# FOTA_Micro_Controller.net
KiCad netlist of a schematic drawn in Altium Designer
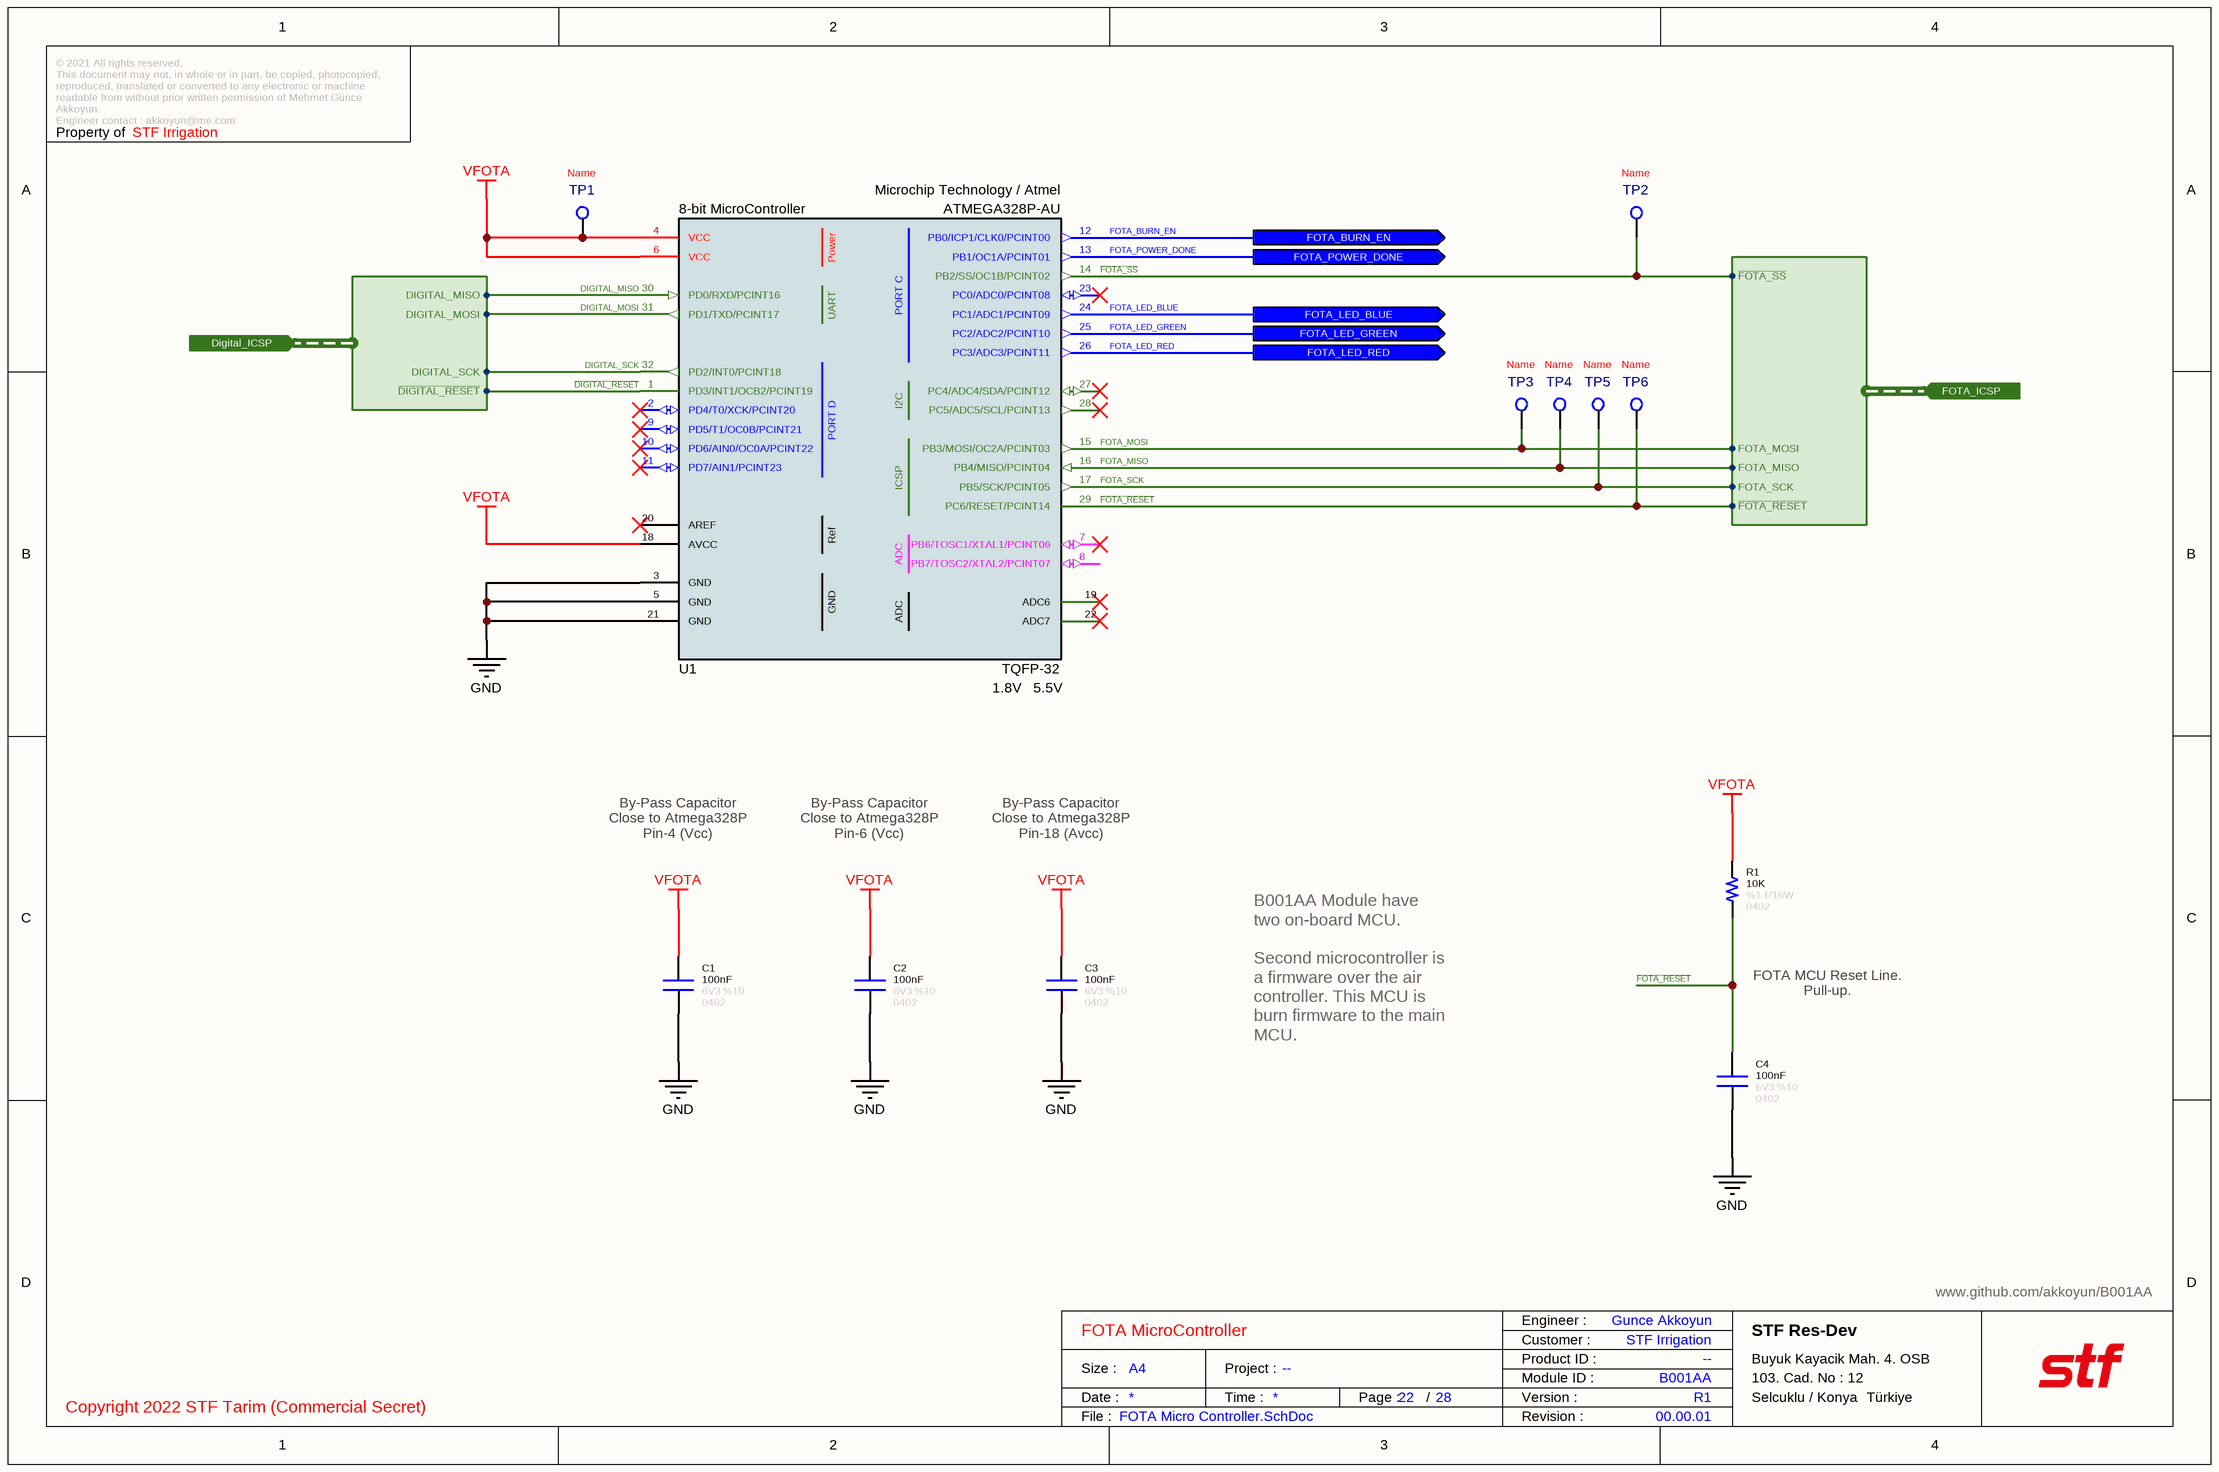
[diagram p0: FOTA Micro Controller.SchDoc]

(export (version "E")
  (design (tool "Eeschema 10.0.6"))
  (components
    (comp (ref "C1")
      (value "100nF")
      (footprint "CAPACITOR_0402")
      (description "Capacitor - 100nF [0402-6V3] (Ceramic)")
      (fields
        (field (name "MANUFACTURER PART NUMBER") "04026D104KAT4A")
        (field (name "TOLERANCE") "%10")
        (field (name "VOLTAGE") "6V3")
        (field (name "CASE") "0402")
        (field (name "Comment") "Capacitor - 100nF [0402] (Ceramic)")
      )
      (libsource (lib "P101DA_Library") (part "Capacitor - 100nF [0402-6V3]"))
    )
    (comp (ref "C2")
      (value "100nF")
      (footprint "CAPACITOR_0402")
      (description "Capacitor - 100nF [0402-6V3] (Ceramic)")
      (fields
        (field (name "MANUFACTURER PART NUMBER") "04026D104KAT4A")
        (field (name "TOLERANCE") "%10")
        (field (name "VOLTAGE") "6V3")
        (field (name "CASE") "0402")
        (field (name "Comment") "Capacitor - 100nF [0402] (Ceramic)")
      )
      (libsource (lib "P101DA_Library") (part "Capacitor - 100nF [0402-6V3]"))
    )
    (comp (ref "C3")
      (value "100nF")
      (footprint "CAPACITOR_0402")
      (description "Capacitor - 100nF [0402-6V3] (Ceramic)")
      (fields
        (field (name "MANUFACTURER PART NUMBER") "04026D104KAT4A")
        (field (name "TOLERANCE") "%10")
        (field (name "VOLTAGE") "6V3")
        (field (name "CASE") "0402")
        (field (name "Comment") "Capacitor - 100nF [0402] (Ceramic)")
      )
      (libsource (lib "P101DA_Library") (part "Capacitor - 100nF [0402-6V3]"))
    )
    (comp (ref "C4")
      (value "100nF")
      (footprint "CAPACITOR_0402")
      (description "Capacitor - 100nF [0402-6V3] (Ceramic)")
      (fields
        (field (name "MANUFACTURER PART NUMBER") "04026D104KAT4A")
        (field (name "TOLERANCE") "%10")
        (field (name "VOLTAGE") "6V3")
        (field (name "CASE") "0402")
        (field (name "Comment") "Capacitor - 100nF [0402] (Ceramic)")
      )
      (libsource (lib "P101DA_Library") (part "Capacitor - 100nF [0402-6V3]"))
    )
    (comp (ref "R1")
      (value "10K")
      (footprint "RESISTOR_0402")
      (description "Thick Film Resistors - SMD 1/16 W 10 KOhm 1%")
      (fields
        (field (name "MANUFACTURER PART NUMBER") "CRCW040210K0FKED")
        (field (name "TOLERANCE") "%1")
        (field (name "CASE") "0402")
        (field (name "POWER") "1/16W")
        (field (name "Comment") "10K - 0402 - %1 - 1/16W")
      )
      (libsource (lib "P101DA_Library") (part "Resistor - 10K [0402]"))
    )
    (comp (ref "TP1")
      (value "PCB - Test Point")
      (footprint "Test_Point")
      (description "Test Point")
      (fields (field (name "NAME") "Name"))
      (libsource (lib "P101DA_Library") (part "PCB - Test Point"))
    )
    (comp (ref "TP2")
      (value "PCB - Test Point")
      (footprint "Test_Point")
      (description "Test Point")
      (fields (field (name "NAME") "Name"))
      (libsource (lib "P101DA_Library") (part "PCB - Test Point"))
    )
    (comp (ref "TP3")
      (value "PCB - Test Point")
      (footprint "Test_Point")
      (description "Test Point")
      (fields (field (name "NAME") "Name"))
      (libsource (lib "P101DA_Library") (part "PCB - Test Point"))
    )
    (comp (ref "TP4")
      (value "PCB - Test Point")
      (footprint "Test_Point")
      (description "Test Point")
      (fields (field (name "NAME") "Name"))
      (libsource (lib "P101DA_Library") (part "PCB - Test Point"))
    )
    (comp (ref "TP5")
      (value "PCB - Test Point")
      (footprint "Test_Point")
      (description "Test Point")
      (fields (field (name "NAME") "Name"))
      (libsource (lib "P101DA_Library") (part "PCB - Test Point"))
    )
    (comp (ref "TP6")
      (value "PCB - Test Point")
      (footprint "Test_Point")
      (description "Test Point")
      (fields (field (name "NAME") "Name"))
      (libsource (lib "P101DA_Library") (part "PCB - Test Point"))
    )
    (comp (ref "U1")
      (value "8-bit MicroController")
      (footprint "TQFN-32")
      (description "8-bit Microcontrollers - MCU 32KB In-system Flash 20MHz 1.8V-5.5V")
      (fields
        (field (name "SUPPLY VOLTAGE - MAX") "5.5V")
        (field (name "SUPPLY VOLTAGE - MIN") "1.8V")
        (field (name "MANUFACTURER NAME") "Microchip Technology / Atmel")
        (field (name "MANUFACTURER PART NUMBER") "ATMEGA328P-AU")
        (field (name "CASE") "TQFP-32")
      )
      (libsource (lib "P101DA_Library") (part "IC - ATMEGA328P-AU"))
    )
  )
  (nets
    (net (code "3") (name "/DIGITAL_MISO") (class "Default")
      (node (ref "U1") (pin "30") (pinfunction "PD0/RXD/PCINT16_30") (pintype "input"))
    )
    (net (code "4") (name "/DIGITAL_MOSI") (class "Default")
      (node (ref "U1") (pin "31") (pinfunction "PD1/TXD/PCINT17_31") (pintype "output"))
    )
    (net (code "5") (name "/DIGITAL_SCK") (class "Default")
      (node (ref "U1") (pin "32") (pinfunction "PD2/INT0/PCINT18_32") (pintype "output"))
    )
    (net (code "6") (name "/FOTA_BURN_EN") (class "Default")
      (node (ref "U1") (pin "12") (pinfunction "PB0/ICP1/CLK0/PCINT00_12") (pintype "output"))
    )
    (net (code "7") (name "/FOTA_LED_BLUE") (class "Default")
      (node (ref "U1") (pin "24") (pinfunction "PC1/ADC1/PCINT09_24") (pintype "output"))
    )
    (net (code "8") (name "/FOTA_LED_GREEN") (class "Default")
      (node (ref "U1") (pin "25") (pinfunction "PC2/ADC2/PCINT10_25") (pintype "output"))
    )
    (net (code "9") (name "/FOTA_LED_RED") (class "Default")
      (node (ref "U1") (pin "26") (pinfunction "PC3/ADC3/PCINT11_26") (pintype "output"))
    )
    (net (code "10") (name "/FOTA_MISO") (class "Default")
      (node (ref "TP4") (pin "1") (pinfunction "1_1") (pintype "passive"))
      (node (ref "U1") (pin "16") (pinfunction "PB4/MISO/PCINT04_16") (pintype "input"))
    )
    (net (code "11") (name "/FOTA_MOSI") (class "Default")
      (node (ref "TP3") (pin "1") (pinfunction "1_1") (pintype "passive"))
      (node (ref "U1") (pin "15") (pinfunction "PB3/MOSI/OC2A/PCINT03_15") (pintype "output"))
    )
    (net (code "12") (name "/FOTA_POWER_DONE") (class "Default")
      (node (ref "U1") (pin "13") (pinfunction "PB1/OC1A/PCINT01_13") (pintype "output"))
    )
    (net (code "13") (name "/FOTA_SCK") (class "Default")
      (node (ref "TP5") (pin "1") (pinfunction "1_1") (pintype "passive"))
      (node (ref "U1") (pin "17") (pinfunction "PB5/SCK/PCINT05_17") (pintype "output"))
    )
    (net (code "16") (name "/~{DIGITAL_RESET}") (class "Default")
      (node (ref "U1") (pin "1") (pinfunction "PD3/INT1/OCB2/PCINT19_1") (pintype "passive"))
    )
    (net (code "17") (name "/~{FOTA_RESET}") (class "Default")
      (node (ref "C4") (pin "2") (pinfunction "2_2") (pintype "passive"))
      (node (ref "R1") (pin "1") (pinfunction "1_1") (pintype "passive"))
      (node (ref "TP6") (pin "1") (pinfunction "1_1") (pintype "passive"))
      (node (ref "U1") (pin "29") (pinfunction "PC6/RESET/PCINT14_29") (pintype "passive"))
    )
    (net (code "18") (name "/~{FOTA_SS}") (class "Default")
      (node (ref "TP2") (pin "1") (pinfunction "1_1") (pintype "passive"))
      (node (ref "U1") (pin "14") (pinfunction "PB2/SS/OC1B/PCINT02_14") (pintype "output"))
    )
    (net (code "19") (name "GND") (class "Default")
      (node (ref "C1") (pin "1") (pinfunction "1_1") (pintype "passive"))
      (node (ref "C2") (pin "1") (pinfunction "1_1") (pintype "passive"))
      (node (ref "C3") (pin "1") (pinfunction "1_1") (pintype "passive"))
      (node (ref "C4") (pin "1") (pinfunction "1_1") (pintype "passive"))
      (node (ref "U1") (pin "21") (pinfunction "GND_21") (pintype "power_in"))
      (node (ref "U1") (pin "3") (pinfunction "GND_3") (pintype "power_in"))
      (node (ref "U1") (pin "5") (pinfunction "GND_5") (pintype "power_in"))
    )
    (net (code "20") (name "VFOTA") (class "Default")
      (node (ref "C1") (pin "2") (pinfunction "2_2") (pintype "passive"))
      (node (ref "C2") (pin "2") (pinfunction "2_2") (pintype "passive"))
      (node (ref "C3") (pin "2") (pinfunction "2_2") (pintype "passive"))
      (node (ref "R1") (pin "2") (pinfunction "2_2") (pintype "passive"))
      (node (ref "TP1") (pin "1") (pinfunction "1_1") (pintype "passive"))
      (node (ref "U1") (pin "18") (pinfunction "AVCC_18") (pintype "passive"))
      (node (ref "U1") (pin "4") (pinfunction "VCC_4") (pintype "power_in"))
      (node (ref "U1") (pin "6") (pinfunction "VCC_6") (pintype "power_in"))
    )
    (net (code "21") (name "unconnected-(U1-ADC6-Pad19)") (class "Default")
      (node (ref "U1") (pin "19") (pinfunction "ADC6_19") (pintype "passive+no_connect"))
    )
    (net (code "22") (name "unconnected-(U1-ADC7-Pad22)") (class "Default")
      (node (ref "U1") (pin "22") (pinfunction "ADC7_22") (pintype "passive+no_connect"))
    )
    (net (code "23") (name "unconnected-(U1-AREF-Pad20)") (class "Default")
      (node (ref "U1") (pin "20") (pinfunction "AREF_20") (pintype "passive+no_connect"))
    )
    (net (code "24") (name "unconnected-(U1-PB6{slash}TOSC1{slash}XTAL1{slash}PCINT06-Pad7)") (class "Default")
      (node (ref "U1") (pin "7") (pinfunction "PB6/TOSC1/XTAL1/PCINT06_7") (pintype "bidirectional+no_connect"))
    )
    (net (code "25") (name "unconnected-(U1-PB7{slash}TOSC2{slash}XTAL2{slash}PCINT07-Pad8)") (class "Default")
      (node (ref "U1") (pin "8") (pinfunction "PB7/TOSC2/XTAL2/PCINT07_8") (pintype "bidirectional"))
    )
    (net (code "26") (name "unconnected-(U1-PC0{slash}ADC0{slash}PCINT08-Pad23)") (class "Default")
      (node (ref "U1") (pin "23") (pinfunction "PC0/ADC0/PCINT08_23") (pintype "bidirectional+no_connect"))
    )
    (net (code "27") (name "unconnected-(U1-PC4{slash}ADC4{slash}SDA{slash}PCINT12-Pad27)") (class "Default")
      (node (ref "U1") (pin "27") (pinfunction "PC4/ADC4/SDA/PCINT12_27") (pintype "bidirectional+no_connect"))
    )
    (net (code "28") (name "unconnected-(U1-PC5{slash}ADC5{slash}SCL{slash}PCINT13-Pad28)") (class "Default")
      (node (ref "U1") (pin "28") (pinfunction "PC5/ADC5/SCL/PCINT13_28") (pintype "output+no_connect"))
    )
    (net (code "29") (name "unconnected-(U1-PD4{slash}T0{slash}XCK{slash}PCINT20-Pad2)") (class "Default")
      (node (ref "U1") (pin "2") (pinfunction "PD4/T0/XCK/PCINT20_2") (pintype "bidirectional+no_connect"))
    )
    (net (code "30") (name "unconnected-(U1-PD5{slash}T1{slash}OC0B{slash}PCINT21-Pad9)") (class "Default")
      (node (ref "U1") (pin "9") (pinfunction "PD5/T1/OC0B/PCINT21_9") (pintype "bidirectional+no_connect"))
    )
    (net (code "31") (name "unconnected-(U1-PD6{slash}AIN0{slash}OC0A{slash}PCINT22-Pad10)") (class "Default")
      (node (ref "U1") (pin "10") (pinfunction "PD6/AIN0/OC0A/PCINT22_10") (pintype "bidirectional+no_connect"))
    )
    (net (code "32") (name "unconnected-(U1-PD7{slash}AIN1{slash}PCINT23-Pad11)") (class "Default")
      (node (ref "U1") (pin "11") (pinfunction "PD7/AIN1/PCINT23_11") (pintype "bidirectional+no_connect"))
    )
  )
)
